# ethernet.net
KiCad netlist of a schematic drawn in Altium Designer
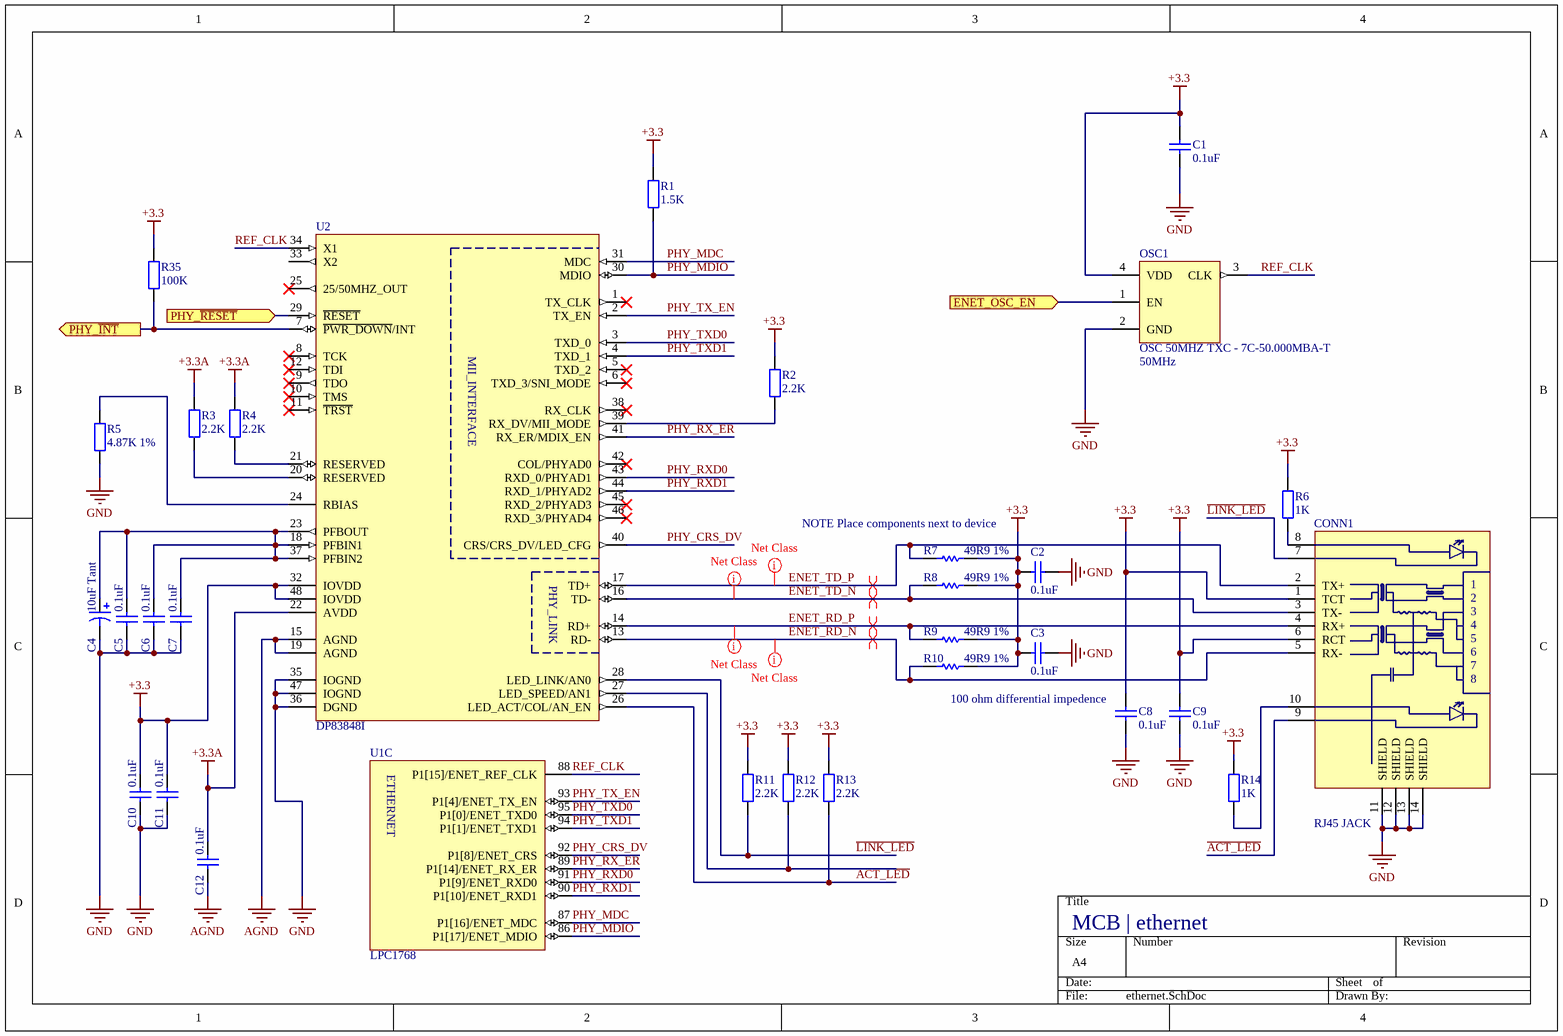
[diagram p0: ethernet.SchDoc]

(export (version "E")
  (design (tool "Eeschema 10.0.6"))
  (components
    (comp (ref "C1")
      (value "0.1uF")
      (footprint "C0603")
      (description "Capacitor")
      (fields (field (name "Comment") "Cap"))
      (libsource (lib "Miscellaneous Devices") (part "Cap"))
    )
    (comp (ref "C2")
      (value "0.1uF")
      (footprint "C0603")
      (description "Capacitor")
      (fields (field (name "Comment") "Cap"))
      (libsource (lib "Miscellaneous Devices") (part "Cap"))
    )
    (comp (ref "C3")
      (value "0.1uF")
      (footprint "C0603")
      (description "Capacitor")
      (fields (field (name "Comment") "Cap"))
      (libsource (lib "Miscellaneous Devices") (part "Cap"))
    )
    (comp (ref "C4")
      (value "10uF Tant")
      (footprint "T491C106K035AT")
      (description "Polarized Capacitor (Radial)")
      (fields (field (name "Comment") "Cap Pol1") (field (name "PUBLISHER") "Altium Limited"))
      (libsource (lib "Miscellaneous Devices") (part "Cap Pol1"))
    )
    (comp (ref "C5")
      (value "0.1uF")
      (footprint "C0603")
      (description "Capacitor")
      (fields (field (name "Comment") "Cap"))
      (libsource (lib "Miscellaneous Devices") (part "Cap"))
    )
    (comp (ref "C6")
      (value "0.1uF")
      (footprint "C0603")
      (description "Capacitor")
      (fields (field (name "Comment") "Cap"))
      (libsource (lib "Miscellaneous Devices") (part "Cap"))
    )
    (comp (ref "C7")
      (value "0.1uF")
      (footprint "C0603")
      (description "Capacitor")
      (fields (field (name "Comment") "Cap"))
      (libsource (lib "Miscellaneous Devices") (part "Cap"))
    )
    (comp (ref "C8")
      (value "0.1uF")
      (footprint "C0603")
      (description "Capacitor")
      (fields (field (name "Comment") "Cap"))
      (libsource (lib "Miscellaneous Devices") (part "Cap"))
    )
    (comp (ref "C9")
      (value "0.1uF")
      (footprint "C0603")
      (description "Capacitor")
      (fields (field (name "Comment") "Cap"))
      (libsource (lib "Miscellaneous Devices") (part "Cap"))
    )
    (comp (ref "C10")
      (value "0.1uF")
      (footprint "C0603")
      (description "Capacitor")
      (fields (field (name "Comment") "Cap"))
      (libsource (lib "Miscellaneous Devices") (part "Cap"))
    )
    (comp (ref "C11")
      (value "0.1uF")
      (footprint "C0603")
      (description "Capacitor")
      (fields (field (name "Comment") "Cap"))
      (libsource (lib "Miscellaneous Devices") (part "Cap"))
    )
    (comp (ref "C12")
      (value "0.1uF")
      (footprint "C0603")
      (description "Capacitor")
      (fields (field (name "Comment") "Cap"))
      (libsource (lib "Miscellaneous Devices") (part "Cap"))
    )
    (comp (ref "CONN1")
      (value "RJ45 JACK")
      (footprint "RJMG163118101NR")
      (description "10/100 BASE T")
      (libsource (lib "mcb") (part "RJ45 JACK"))
    )
    (comp (ref "OSC1")
      (value "OSC 50MHZ TXC - 7C-50.000MBA-T")
      (footprint "7C-50.000MBA-T")
      (description "TXC - 7C-50.000MBA-T - OSC, 50.000MHZ, 3.3V, SMD, 5.0X3.2")
      (fields (field (name "ALTIUM_VALUE") "50MHz"))
      (libsource (lib "OSC 50MHZ TXC - 7C-50.000MBA-T - OSC, 50.000MHZ, 3.3V, SMD, 5.0X3.2") (part "OSC 50MHZ TXC - 7C-50.000MBA-T"))
    )
    (comp (ref "R1")
      (value "1.5K")
      (footprint "R0603")
      (description "Resistor")
      (fields (field (name "Comment") "Res"))
      (libsource (lib "Miscellaneous Devices") (part "Res2"))
    )
    (comp (ref "R2")
      (value "2.2K")
      (footprint "R0603")
      (description "Resistor")
      (fields (field (name "Comment") "Res"))
      (libsource (lib "Miscellaneous Devices") (part "Res2"))
    )
    (comp (ref "R3")
      (value "2.2K")
      (footprint "R0603")
      (description "Resistor")
      (fields (field (name "Comment") "Res"))
      (libsource (lib "Miscellaneous Devices") (part "Res2"))
    )
    (comp (ref "R4")
      (value "2.2K")
      (footprint "R0603")
      (description "Resistor")
      (fields (field (name "Comment") "Res"))
      (libsource (lib "Miscellaneous Devices") (part "Res2"))
    )
    (comp (ref "R5")
      (value "4.87K 1%")
      (footprint "R0603")
      (description "Resistor")
      (fields (field (name "Comment") "Res"))
      (libsource (lib "Miscellaneous Devices") (part "Res2"))
    )
    (comp (ref "R6")
      (value "1K")
      (footprint "R0603")
      (description "Resistor")
      (fields (field (name "Comment") "Res"))
      (libsource (lib "Miscellaneous Devices") (part "Res2"))
    )
    (comp (ref "R7")
      (value "49R9 1%")
      (footprint "R0603")
      (description "Resistor")
      (fields (field (name "Comment") "Res"))
      (libsource (lib "Miscellaneous Devices") (part "Res1"))
    )
    (comp (ref "R8")
      (value "49R9 1%")
      (footprint "R0603")
      (description "Resistor")
      (fields (field (name "Comment") "Res"))
      (libsource (lib "Miscellaneous Devices") (part "Res1"))
    )
    (comp (ref "R9")
      (value "49R9 1%")
      (footprint "R0603")
      (description "Resistor")
      (fields (field (name "Comment") "Res"))
      (libsource (lib "Miscellaneous Devices") (part "Res1"))
    )
    (comp (ref "R10")
      (value "49R9 1%")
      (footprint "R0603")
      (description "Resistor")
      (fields (field (name "Comment") "Res"))
      (libsource (lib "Miscellaneous Devices") (part "Res1"))
    )
    (comp (ref "R11")
      (value "2.2K")
      (footprint "R0603")
      (description "Resistor")
      (fields (field (name "Comment") "Res"))
      (libsource (lib "Miscellaneous Devices") (part "Res2"))
    )
    (comp (ref "R12")
      (value "2.2K")
      (footprint "R0603")
      (description "Resistor")
      (fields (field (name "Comment") "Res"))
      (libsource (lib "Miscellaneous Devices") (part "Res2"))
    )
    (comp (ref "R13")
      (value "2.2K")
      (footprint "R0603")
      (description "Resistor")
      (fields (field (name "Comment") "Res"))
      (libsource (lib "Miscellaneous Devices") (part "Res2"))
    )
    (comp (ref "R14")
      (value "1K")
      (footprint "R0603")
      (description "Resistor")
      (fields (field (name "Comment") "Res"))
      (libsource (lib "Miscellaneous Devices") (part "Res2"))
    )
    (comp (ref "R35")
      (value "100K")
      (footprint "R0603")
      (description "Resistor")
      (fields (field (name "Comment") "Res"))
      (libsource (lib "Miscellaneous Devices") (part "Res2"))
    )
    (comp (ref "U1") (value "LPC1768") (footprint "LPC1768") (libsource (lib "mcb") (part "LPC1768")))
    (comp (ref "U2")
      (value "DP83848I")
      (footprint "DP83848IVV")
      (description "100mbit Ethernet PHY")
      (libsource (lib "DP83848I") (part "DP83848I"))
    )
  )
  (nets
    (net (code "1") (name "+3.3") (class "Default")
      (node (ref "C1") (pin "2") (pinfunction "2_2") (pintype "passive"))
      (node (ref "C10") (pin "1") (pinfunction "1_1") (pintype "passive"))
      (node (ref "C11") (pin "1") (pinfunction "1_1") (pintype "passive"))
      (node (ref "C2") (pin "1") (pinfunction "1_1") (pintype "passive"))
      (node (ref "C3") (pin "1") (pinfunction "1_1") (pintype "passive"))
      (node (ref "C8") (pin "2") (pinfunction "2_2") (pintype "passive"))
      (node (ref "C9") (pin "2") (pinfunction "2_2") (pintype "passive"))
      (node (ref "CONN1") (pin "1") (pinfunction "TCT_1") (pintype "passive"))
      (node (ref "CONN1") (pin "6") (pinfunction "RCT_6") (pintype "passive"))
      (node (ref "OSC1") (pin "4") (pinfunction "VDD_4") (pintype "power_in"))
      (node (ref "R1") (pin "2") (pinfunction "2_2") (pintype "passive"))
      (node (ref "R10") (pin "2") (pinfunction "2_2") (pintype "passive"))
      (node (ref "R11") (pin "2") (pinfunction "2_2") (pintype "passive"))
      (node (ref "R12") (pin "2") (pinfunction "2_2") (pintype "passive"))
      (node (ref "R13") (pin "2") (pinfunction "2_2") (pintype "passive"))
      (node (ref "R14") (pin "2") (pinfunction "2_2") (pintype "passive"))
      (node (ref "R2") (pin "2") (pinfunction "2_2") (pintype "passive"))
      (node (ref "R35") (pin "2") (pinfunction "2_2") (pintype "passive"))
      (node (ref "R6") (pin "2") (pinfunction "2_2") (pintype "passive"))
      (node (ref "R7") (pin "2") (pinfunction "2_2") (pintype "passive"))
      (node (ref "R8") (pin "2") (pinfunction "2_2") (pintype "passive"))
      (node (ref "R9") (pin "2") (pinfunction "2_2") (pintype "passive"))
      (node (ref "U2") (pin "32") (pinfunction "IOVDD_32") (pintype "power_in"))
      (node (ref "U2") (pin "48") (pinfunction "IOVDD_48") (pintype "power_in"))
    )
    (net (code "2") (name "+3.3A") (class "Default")
      (node (ref "C12") (pin "1") (pinfunction "1_1") (pintype "passive"))
      (node (ref "R3") (pin "2") (pinfunction "2_2") (pintype "passive"))
      (node (ref "R4") (pin "2") (pinfunction "2_2") (pintype "passive"))
      (node (ref "U2") (pin "22") (pinfunction "AVDD_22") (pintype "power_in"))
    )
    (net (code "3") (name "/ENET_OSC_EN") (class "Default")
      (node (ref "OSC1") (pin "1") (pinfunction "EN_1") (pintype "passive"))
    )
    (net (code "4") (name "/ENET_RD_N") (class "Default")
      (node (ref "CONN1") (pin "5") (pinfunction "RX-_5") (pintype "passive"))
      (node (ref "R10") (pin "1") (pinfunction "1_1") (pintype "passive"))
      (node (ref "U2") (pin "13") (pinfunction "RD-_13") (pintype "bidirectional"))
    )
    (net (code "5") (name "/ENET_RD_P") (class "Default")
      (node (ref "CONN1") (pin "4") (pinfunction "RX+_4") (pintype "passive"))
      (node (ref "R9") (pin "1") (pinfunction "1_1") (pintype "passive"))
      (node (ref "U2") (pin "14") (pinfunction "RD+_14") (pintype "bidirectional"))
    )
    (net (code "6") (name "/ENET_TD_N") (class "Default")
      (node (ref "CONN1") (pin "3") (pinfunction "TX-_3") (pintype "passive"))
      (node (ref "R8") (pin "1") (pinfunction "1_1") (pintype "passive"))
      (node (ref "U2") (pin "16") (pinfunction "TD-_16") (pintype "bidirectional"))
    )
    (net (code "7") (name "/ENET_TD_P") (class "Default")
      (node (ref "CONN1") (pin "2") (pinfunction "TX+_2") (pintype "passive"))
      (node (ref "R7") (pin "1") (pinfunction "1_1") (pintype "passive"))
      (node (ref "U2") (pin "17") (pinfunction "TD+_17") (pintype "bidirectional"))
    )
    (net (code "8") (name "/PHY_CRS_DV") (class "Default")
      (node (ref "U1") (pin "92") (pinfunction "P1[8]/ENET_CRS_92") (pintype "bidirectional"))
      (node (ref "U2") (pin "40") (pinfunction "CRS/CRS_DV/LED_CFG_40") (pintype "output"))
    )
    (net (code "9") (name "/PHY_MDC") (class "Default")
      (node (ref "U1") (pin "87") (pinfunction "P1[16]/ENET_MDC_87") (pintype "bidirectional"))
      (node (ref "U2") (pin "31") (pinfunction "MDC_31") (pintype "input"))
    )
    (net (code "10") (name "/PHY_MDIO") (class "Default")
      (node (ref "R1") (pin "1") (pinfunction "1_1") (pintype "passive"))
      (node (ref "U1") (pin "86") (pinfunction "P1[17]/ENET_MDIO_86") (pintype "bidirectional"))
      (node (ref "U2") (pin "30") (pinfunction "MDIO_30") (pintype "bidirectional"))
    )
    (net (code "11") (name "/PHY_RXD0") (class "Default")
      (node (ref "U1") (pin "91") (pinfunction "P1[9]/ENET_RXD0_91") (pintype "bidirectional"))
      (node (ref "U2") (pin "43") (pinfunction "RXD_0/PHYAD1_43") (pintype "output"))
    )
    (net (code "12") (name "/PHY_RXD1") (class "Default")
      (node (ref "U1") (pin "90") (pinfunction "P1[10]/ENET_RXD1_90") (pintype "bidirectional"))
      (node (ref "U2") (pin "44") (pinfunction "RXD_1/PHYAD2_44") (pintype "output"))
    )
    (net (code "13") (name "/PHY_RX_ER") (class "Default")
      (node (ref "U1") (pin "89") (pinfunction "P1[14]/ENET_RX_ER_89") (pintype "bidirectional"))
      (node (ref "U2") (pin "41") (pinfunction "RX_ER/MDIX_EN_41") (pintype "output"))
    )
    (net (code "14") (name "/PHY_TXD0") (class "Default")
      (node (ref "U1") (pin "95") (pinfunction "P1[0]/ENET_TXD0_95") (pintype "bidirectional"))
      (node (ref "U2") (pin "3") (pinfunction "TXD_0_3") (pintype "input"))
    )
    (net (code "15") (name "/PHY_TXD1") (class "Default")
      (node (ref "U1") (pin "94") (pinfunction "P1[1]/ENET_TXD1_94") (pintype "bidirectional"))
      (node (ref "U2") (pin "4") (pinfunction "TXD_1_4") (pintype "input"))
    )
    (net (code "16") (name "/PHY_TX_EN") (class "Default")
      (node (ref "U1") (pin "93") (pinfunction "P1[4]/ENET_TX_EN_93") (pintype "bidirectional"))
      (node (ref "U2") (pin "2") (pinfunction "TX_EN_2") (pintype "input"))
    )
    (net (code "17") (name "/PHY_~{INT}") (class "Default")
      (node (ref "R35") (pin "1") (pinfunction "1_1") (pintype "passive"))
      (node (ref "U2") (pin "7") (pinfunction "~{PWR_DOWN}/INT_7") (pintype "bidirectional"))
    )
    (net (code "18") (name "/PHY_~{RESET}") (class "Default")
      (node (ref "U2") (pin "29") (pinfunction "~{RESET}_29") (pintype "input"))
    )
    (net (code "19") (name "/REF_CLK") (class "Default")
      (node (ref "OSC1") (pin "3") (pinfunction "CLK_3") (pintype "output"))
      (node (ref "U1") (pin "88") (pinfunction "P1[15]/ENET_REF_CLK_88") (pintype "passive"))
      (node (ref "U2") (pin "34") (pinfunction "X1_34") (pintype "input"))
    )
    (net (code "20") (name "/~{ACT_LED}") (class "Default")
      (node (ref "CONN1") (pin "9") (pintype "passive"))
      (node (ref "R13") (pin "1") (pinfunction "1_1") (pintype "passive"))
      (node (ref "U2") (pin "26") (pinfunction "LED_ACT/COL/AN_EN_26") (pintype "output"))
    )
    (net (code "21") (name "/~{LINK_LED}") (class "Default")
      (node (ref "CONN1") (pin "7") (pintype "passive"))
      (node (ref "R11") (pin "1") (pinfunction "1_1") (pintype "passive"))
      (node (ref "U2") (pin "28") (pinfunction "LED_LINK/AN0_28") (pintype "output"))
    )
    (net (code "22") (name "AGND") (class "Default")
      (node (ref "C12") (pin "2") (pinfunction "2_2") (pintype "passive"))
      (node (ref "U2") (pin "15") (pinfunction "AGND_15") (pintype "power_in"))
      (node (ref "U2") (pin "19") (pinfunction "AGND_19") (pintype "power_in"))
    )
    (net (code "23") (name "GND") (class "Default")
      (node (ref "C1") (pin "1") (pinfunction "1_1") (pintype "passive"))
      (node (ref "C10") (pin "2") (pinfunction "2_2") (pintype "passive"))
      (node (ref "C11") (pin "2") (pinfunction "2_2") (pintype "passive"))
      (node (ref "C2") (pin "2") (pinfunction "2_2") (pintype "passive"))
      (node (ref "C3") (pin "2") (pinfunction "2_2") (pintype "passive"))
      (node (ref "C4") (pin "2") (pinfunction "2_2") (pintype "passive"))
      (node (ref "C5") (pin "2") (pinfunction "2_2") (pintype "passive"))
      (node (ref "C6") (pin "2") (pinfunction "2_2") (pintype "passive"))
      (node (ref "C7") (pin "2") (pinfunction "2_2") (pintype "passive"))
      (node (ref "C8") (pin "1") (pinfunction "1_1") (pintype "passive"))
      (node (ref "C9") (pin "1") (pinfunction "1_1") (pintype "passive"))
      (node (ref "CONN1") (pin "11") (pinfunction "SHIELD_11") (pintype "power_in"))
      (node (ref "CONN1") (pin "12") (pinfunction "SHIELD_12") (pintype "power_in"))
      (node (ref "CONN1") (pin "13") (pinfunction "SHIELD_13") (pintype "power_in"))
      (node (ref "CONN1") (pin "14") (pinfunction "SHIELD_14") (pintype "power_in"))
      (node (ref "OSC1") (pin "2") (pinfunction "GND_2") (pintype "power_in"))
      (node (ref "R5") (pin "1") (pinfunction "1_1") (pintype "passive"))
      (node (ref "U2") (pin "35") (pinfunction "IOGND_35") (pintype "power_in"))
      (node (ref "U2") (pin "36") (pinfunction "DGND_36") (pintype "power_in"))
      (node (ref "U2") (pin "47") (pinfunction "IOGND_47") (pintype "power_in"))
    )
    (net (code "24") (name "Net-(CONN1-Pad8)") (class "Default")
      (node (ref "CONN1") (pin "8") (pintype "passive"))
      (node (ref "R6") (pin "1") (pinfunction "1_1") (pintype "passive"))
    )
    (net (code "25") (name "Net-(CONN1-Pad10)") (class "Default")
      (node (ref "CONN1") (pin "10") (pintype "passive"))
      (node (ref "R14") (pin "1") (pinfunction "1_1") (pintype "passive"))
    )
    (net (code "26") (name "Net-(R3-Pad1)") (class "Default")
      (node (ref "R3") (pin "1") (pinfunction "1_1") (pintype "passive"))
      (node (ref "U2") (pin "20") (pinfunction "RESERVED_20") (pintype "bidirectional"))
    )
    (net (code "27") (name "Net-(R4-Pad1)") (class "Default")
      (node (ref "R4") (pin "1") (pinfunction "1_1") (pintype "passive"))
      (node (ref "U2") (pin "21") (pinfunction "RESERVED_21") (pintype "bidirectional"))
    )
    (net (code "28") (name "Net-(U2-LED_SPEED{slash}AN1)") (class "Default")
      (node (ref "R12") (pin "1") (pinfunction "1_1") (pintype "passive"))
      (node (ref "U2") (pin "27") (pinfunction "LED_SPEED/AN1_27") (pintype "output"))
    )
    (net (code "29") (name "Net-(U2-PFBIN1)") (class "Default")
      (node (ref "C4") (pin "1") (pinfunction "1_1") (pintype "passive"))
      (node (ref "C5") (pin "1") (pinfunction "1_1") (pintype "passive"))
      (node (ref "C6") (pin "1") (pinfunction "1_1") (pintype "passive"))
      (node (ref "C7") (pin "1") (pinfunction "1_1") (pintype "passive"))
      (node (ref "U2") (pin "18") (pinfunction "PFBIN1_18") (pintype "input"))
      (node (ref "U2") (pin "23") (pinfunction "PFBOUT_23") (pintype "output"))
      (node (ref "U2") (pin "37") (pinfunction "PFBIN2_37") (pintype "input"))
    )
    (net (code "30") (name "Net-(U2-RBIAS)") (class "Default")
      (node (ref "R5") (pin "2") (pinfunction "2_2") (pintype "passive"))
      (node (ref "U2") (pin "24") (pinfunction "RBIAS_24") (pintype "passive"))
    )
    (net (code "31") (name "Net-(U2-RX_DV{slash}MII_MODE)") (class "Default")
      (node (ref "R2") (pin "1") (pinfunction "1_1") (pintype "passive"))
      (node (ref "U2") (pin "39") (pinfunction "RX_DV/MII_MODE_39") (pintype "output"))
    )
    (net (code "32") (name "unconnected-(U2-25{slash}50MHZ_OUT-Pad25)") (class "Default")
      (node (ref "U2") (pin "25") (pinfunction "25/50MHZ_OUT_25") (pintype "output+no_connect"))
    )
    (net (code "33") (name "unconnected-(U2-COL{slash}PHYAD0-Pad42)") (class "Default")
      (node (ref "U2") (pin "42") (pinfunction "COL/PHYAD0_42") (pintype "output+no_connect"))
    )
    (net (code "34") (name "unconnected-(U2-RXD_2{slash}PHYAD3-Pad45)") (class "Default")
      (node (ref "U2") (pin "45") (pinfunction "RXD_2/PHYAD3_45") (pintype "output+no_connect"))
    )
    (net (code "35") (name "unconnected-(U2-RXD_3{slash}PHYAD4-Pad46)") (class "Default")
      (node (ref "U2") (pin "46") (pinfunction "RXD_3/PHYAD4_46") (pintype "output+no_connect"))
    )
    (net (code "36") (name "unconnected-(U2-RX_CLK-Pad38)") (class "Default")
      (node (ref "U2") (pin "38") (pinfunction "RX_CLK_38") (pintype "output+no_connect"))
    )
    (net (code "37") (name "unconnected-(U2-TCK-Pad8)") (class "Default")
      (node (ref "U2") (pin "8") (pinfunction "TCK_8") (pintype "input+no_connect"))
    )
    (net (code "38") (name "unconnected-(U2-TDI-Pad12)") (class "Default")
      (node (ref "U2") (pin "12") (pinfunction "TDI_12") (pintype "input+no_connect"))
    )
    (net (code "39") (name "unconnected-(U2-TDO-Pad9)") (class "Default")
      (node (ref "U2") (pin "9") (pinfunction "TDO_9") (pintype "output+no_connect"))
    )
    (net (code "40") (name "unconnected-(U2-TMS-Pad10)") (class "Default")
      (node (ref "U2") (pin "10") (pinfunction "TMS_10") (pintype "input+no_connect"))
    )
    (net (code "41") (name "unconnected-(U2-TXD_2-Pad5)") (class "Default")
      (node (ref "U2") (pin "5") (pinfunction "TXD_2_5") (pintype "input+no_connect"))
    )
    (net (code "42") (name "unconnected-(U2-TXD_3{slash}SNI_MODE-Pad6)") (class "Default")
      (node (ref "U2") (pin "6") (pinfunction "TXD_3/SNI_MODE_6") (pintype "input+no_connect"))
    )
    (net (code "43") (name "unconnected-(U2-TX_CLK-Pad1)") (class "Default")
      (node (ref "U2") (pin "1") (pinfunction "TX_CLK_1") (pintype "output+no_connect"))
    )
    (net (code "44") (name "unconnected-(U2-X2-Pad33)") (class "Default")
      (node (ref "U2") (pin "33") (pinfunction "X2_33") (pintype "output"))
    )
    (net (code "45") (name "unconnected-(U2-~{TRST}-Pad11)") (class "Default")
      (node (ref "U2") (pin "11") (pinfunction "~{TRST}_11") (pintype "input+no_connect"))
    )
  )
)
